# 5V_LED_Indicator.net
KiCad netlist of a schematic drawn in Altium Designer
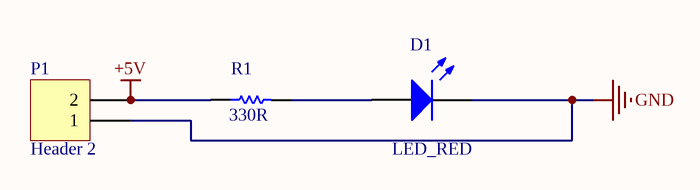
[diagram p0: 5V_LED_Indicator.SchDoc]

(export (version "E")
  (design (tool "Eeschema 10.0.6"))
  (components
    (comp (ref "D1")
      (value "LED_RED")
      (footprint "LED-1")
      (description "Light-Emitting Diode")
      (libsource (lib "Simulation Generic Components") (part "LED"))
    )
    (comp (ref "P1")
      (value "Header 2")
      (footprint "HDR1X2")
      (description "Header, 2-Pin")
      (fields (field (name "PUBLISHER") "Altium Limited"))
      (libsource (lib "Miscellaneous Connectors") (part "Header 2"))
    )
    (comp (ref "R1")
      (value "330R")
      (footprint "AXIAL-0.3")
      (description "Resistor")
      (libsource (lib "Simulation Generic Components") (part "Resistor"))
    )
  )
  (nets
    (net (code "1") (name "+5V") (class "Default")
      (node (ref "P1") (pin "2") (pinfunction "2_2") (pintype "passive"))
      (node (ref "R1") (pin "1") (pinfunction "1_1") (pintype "passive"))
    )
    (net (code "2") (name "GND") (class "Default")
      (node (ref "D1") (pin "2") (pinfunction "K_2") (pintype "passive"))
      (node (ref "P1") (pin "1") (pinfunction "1_1") (pintype "passive"))
    )
    (net (code "3") (name "Net-(D1-A)") (class "Default")
      (node (ref "D1") (pin "1") (pinfunction "A_1") (pintype "passive"))
      (node (ref "R1") (pin "2") (pinfunction "2_2") (pintype "passive"))
    )
  )
)
